# ST_Board.net
KiCad netlist of a schematic drawn in Altium Designer
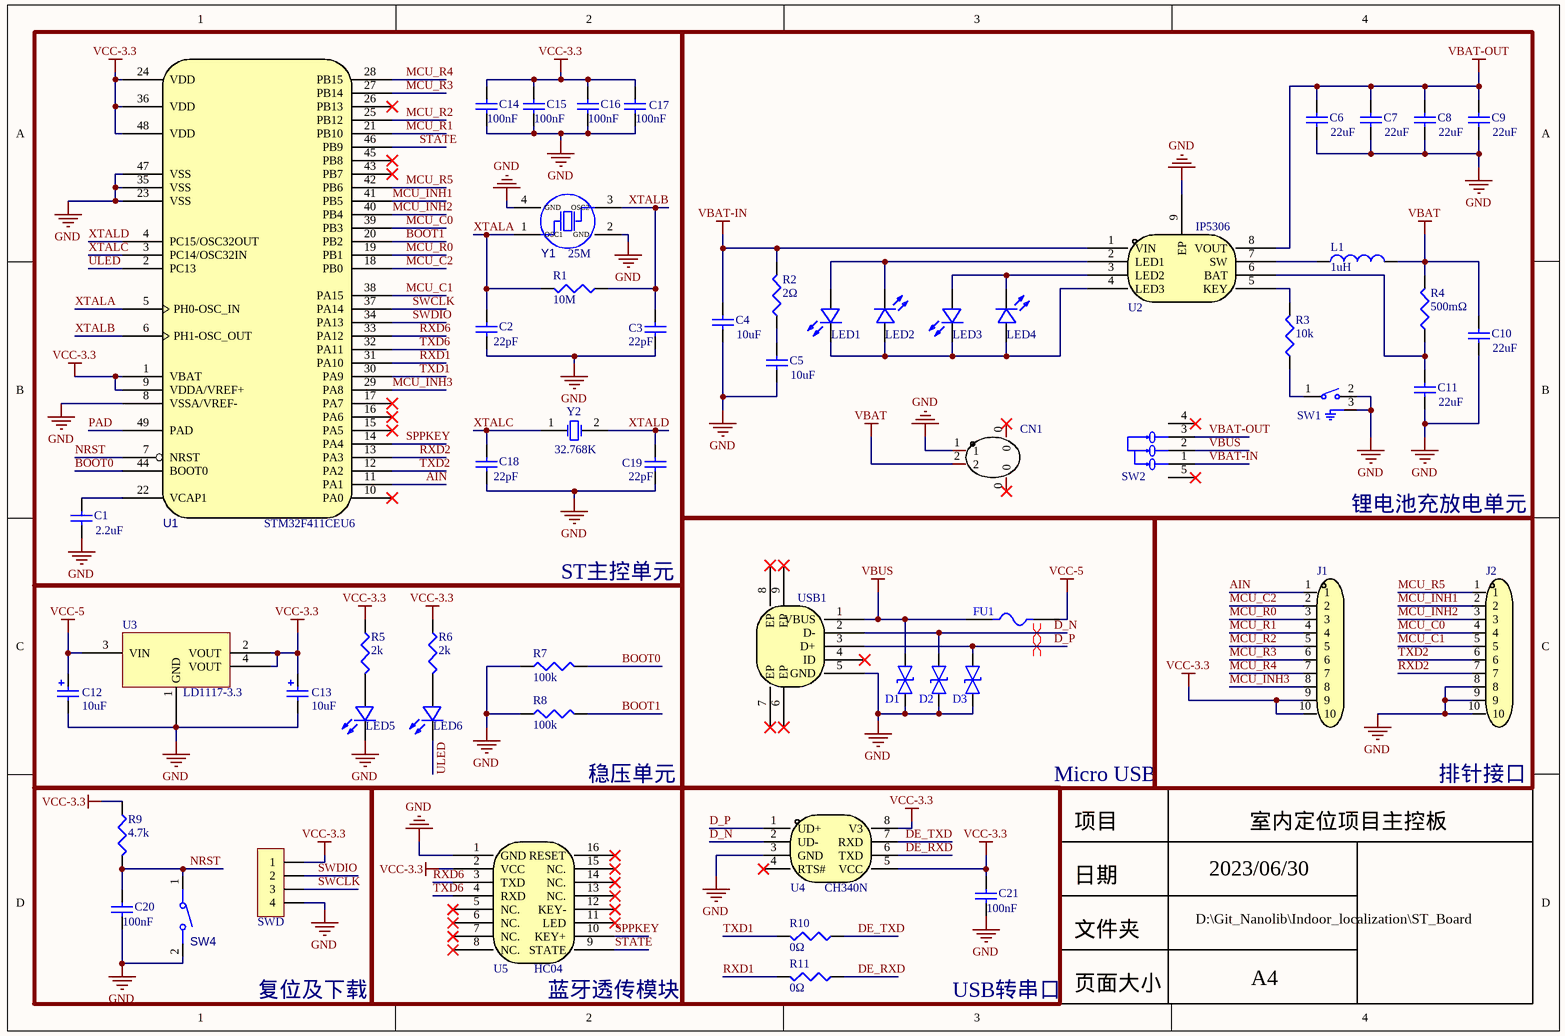
[diagram p0: ST_Board.SchDoc]

(export (version "E")
  (design (tool "Eeschema 10.0.6"))
  (components
    (comp (ref "C1")
      (value "2.2uF")
      (footprint "C0603")
      (description "Capacitor")
      (fields (field (name "Comment") "Cap") (field (name "PUBLISHER") "Altium Limited"))
      (libsource (lib "Miscellaneous Devices") (part "Cap"))
    )
    (comp (ref "C2")
      (value "22pF")
      (footprint "C0603")
      (description "Capacitor")
      (fields (field (name "Comment") "Cap") (field (name "PUBLISHER") "Altium Limited"))
      (libsource (lib "Miscellaneous Devices") (part "Cap"))
    )
    (comp (ref "C3")
      (value "22pF")
      (footprint "C0603")
      (description "Capacitor")
      (fields (field (name "Comment") "Cap") (field (name "PUBLISHER") "Altium Limited"))
      (libsource (lib "Miscellaneous Devices") (part "Cap"))
    )
    (comp (ref "C4")
      (value "10uF")
      (footprint "C0603")
      (description "Capacitor")
      (fields (field (name "Comment") "Cap") (field (name "PUBLISHER") "Altium Limited"))
      (libsource (lib "Miscellaneous Devices") (part "Cap"))
    )
    (comp (ref "C5")
      (value "10uF")
      (footprint "C0603")
      (description "Capacitor")
      (fields (field (name "Comment") "Cap") (field (name "PUBLISHER") "Altium Limited"))
      (libsource (lib "Miscellaneous Devices") (part "Cap"))
    )
    (comp (ref "C6")
      (value "22uF")
      (footprint "C1206")
      (description "Capacitor")
      (fields (field (name "Comment") "Cap") (field (name "PUBLISHER") "Altium Limited"))
      (libsource (lib "Miscellaneous Devices") (part "Cap"))
    )
    (comp (ref "C7")
      (value "22uF")
      (footprint "C1206")
      (description "Capacitor")
      (fields (field (name "Comment") "Cap") (field (name "PUBLISHER") "Altium Limited"))
      (libsource (lib "Miscellaneous Devices") (part "Cap"))
    )
    (comp (ref "C8")
      (value "22uF")
      (footprint "C1206")
      (description "Capacitor")
      (fields (field (name "Comment") "Cap") (field (name "PUBLISHER") "Altium Limited"))
      (libsource (lib "Miscellaneous Devices") (part "Cap"))
    )
    (comp (ref "C9")
      (value "22uF")
      (footprint "C1206")
      (description "Capacitor")
      (fields (field (name "Comment") "Cap") (field (name "PUBLISHER") "Altium Limited"))
      (libsource (lib "Miscellaneous Devices") (part "Cap"))
    )
    (comp (ref "C10")
      (value "22uF")
      (footprint "C1206")
      (description "Capacitor")
      (fields (field (name "Comment") "Cap") (field (name "PUBLISHER") "Altium Limited"))
      (libsource (lib "Miscellaneous Devices") (part "Cap"))
    )
    (comp (ref "C11")
      (value "22uF")
      (footprint "C1206")
      (description "Capacitor")
      (fields (field (name "Comment") "Cap") (field (name "PUBLISHER") "Altium Limited"))
      (libsource (lib "Miscellaneous Devices") (part "Cap"))
    )
    (comp (ref "C12")
      (value "10uF")
      (footprint "CAP-SMD_L3.2-W1.6-RD-C7171")
      (description "贴片钽电容")
      (fields (field (name "MANUFACTURER") "Kyocera AVX") (field (name "MANUFACTURER PART") "TAJA106K016RNJ"))
      (libsource (lib "Passive_Device") (part "Cap-TAJA"))
    )
    (comp (ref "C13")
      (value "10uF")
      (footprint "CAP-SMD_L3.2-W1.6-RD-C7171")
      (description "贴片钽电容")
      (fields (field (name "MANUFACTURER") "Kyocera AVX") (field (name "MANUFACTURER PART") "TAJA106K016RNJ"))
      (libsource (lib "Passive_Device") (part "Cap-TAJA"))
    )
    (comp (ref "C14")
      (value "100nF")
      (footprint "C0603")
      (description "Capacitor")
      (fields (field (name "Comment") "Cap") (field (name "PUBLISHER") "Altium Limited"))
      (libsource (lib "Miscellaneous Devices") (part "Cap"))
    )
    (comp (ref "C15")
      (value "100nF")
      (footprint "C0603")
      (description "Capacitor")
      (fields (field (name "Comment") "Cap") (field (name "PUBLISHER") "Altium Limited"))
      (libsource (lib "Miscellaneous Devices") (part "Cap"))
    )
    (comp (ref "C16")
      (value "100nF")
      (footprint "C0603")
      (description "Capacitor")
      (fields (field (name "Comment") "Cap") (field (name "PUBLISHER") "Altium Limited"))
      (libsource (lib "Miscellaneous Devices") (part "Cap"))
    )
    (comp (ref "C17")
      (value "100nF")
      (footprint "C0603")
      (description "Capacitor")
      (fields (field (name "Comment") "Cap") (field (name "PUBLISHER") "Altium Limited"))
      (libsource (lib "Miscellaneous Devices") (part "Cap"))
    )
    (comp (ref "C18")
      (value "22pF")
      (footprint "C0603")
      (description "Capacitor")
      (fields (field (name "Comment") "Cap") (field (name "PUBLISHER") "Altium Limited"))
      (libsource (lib "Miscellaneous Devices") (part "Cap"))
    )
    (comp (ref "C19")
      (value "22pF")
      (footprint "C0603")
      (description "Capacitor")
      (fields (field (name "Comment") "Cap") (field (name "PUBLISHER") "Altium Limited"))
      (libsource (lib "Miscellaneous Devices") (part "Cap"))
    )
    (comp (ref "C20")
      (value "100nF")
      (footprint "C0603")
      (description "Capacitor")
      (fields (field (name "Comment") "Cap") (field (name "PUBLISHER") "Altium Limited"))
      (libsource (lib "Miscellaneous Devices") (part "Cap"))
    )
    (comp (ref "C21")
      (value "100nF")
      (footprint "C0603")
      (description "Capacitor")
      (fields (field (name "Comment") "Cap") (field (name "PUBLISHER") "Altium Limited"))
      (libsource (lib "Miscellaneous Devices") (part "Cap"))
    )
    (comp (ref "CN1")
      (value "1.0T-2P卧贴")
      (footprint "CONN-SMD_1.0T-2P")
      (description "锂电池接口")
      (fields (field (name "MANUFACTURER") "BOOMELE(博穆精密)"))
      (libsource (lib "Component") (part "1.0T-2P卧贴"))
    )
    (comp (ref "D1")
      (value "LESD5D5.0CT1G")
      (footprint "SOD-523_L1.2-W0.8-LS1.6-BI")
      (description "静电放电(ESD)保护器件")
      (fields (field (name "DESIGNER") "U?"))
      (libsource (lib "Passive_Device") (part "LESD5D5.0CT1G"))
    )
    (comp (ref "D2")
      (value "LESD5D5.0CT1G")
      (footprint "SOD-523_L1.2-W0.8-LS1.6-BI")
      (description "静电放电(ESD)保护器件")
      (fields (field (name "DESIGNER") "U?"))
      (libsource (lib "Passive_Device") (part "LESD5D5.0CT1G"))
    )
    (comp (ref "D3")
      (value "LESD5D5.0CT1G")
      (footprint "SOD-523_L1.2-W0.8-LS1.6-BI")
      (description "静电放电(ESD)保护器件")
      (fields (field (name "DESIGNER") "U?"))
      (libsource (lib "Passive_Device") (part "LESD5D5.0CT1G"))
    )
    (comp (ref "FU1")
      (value "FUSE 1A")
      (footprint "F0805")
      (description "贴片保险丝")
      (fields (field (name "MANUFACTURER") "RUILON(瑞隆源)") (field (name "MANUFACTURER PART") "SMD0805P075TF"))
      (libsource (lib "Passive_Device") (part "FU"))
    )
    (comp (ref "J1")
      (value "Header 10X1")
      (footprint "HDR-TH_10P-P2.54-V-M")
      (description "10P*1接插件")
      (fields (field (name "DESIGNER") "U?"))
      (libsource (lib "Connector") (part "Header 10X1"))
    )
    (comp (ref "J2")
      (value "Header 10X1")
      (footprint "HDR-TH_10P-P2.54-V-M")
      (description "10P*1接插件")
      (fields (field (name "DESIGNER") "U?"))
      (libsource (lib "Connector") (part "Header 10X1"))
    )
    (comp (ref "L1")
      (value "1uH")
      (footprint "IND-SMD_L6.5-W6.5_IHLP-2525")
      (description "Inductor")
      (fields (field (name "PUBLISHER") "Altium Limited"))
      (libsource (lib "Miscellaneous Devices") (part "Inductor"))
    )
    (comp (ref "LED1")
      (value "NCD0603G2")
      (footprint "LED0603-RD")
      (fields (field (name "MANUFACTURER") "国星光电"))
      (libsource (lib "Component") (part "NCD0603G2"))
    )
    (comp (ref "LED2")
      (value "NCD0603G2")
      (footprint "LED0603-RD")
      (fields (field (name "MANUFACTURER") "国星光电"))
      (libsource (lib "Component") (part "NCD0603G2"))
    )
    (comp (ref "LED3")
      (value "NCD0603G2")
      (footprint "LED0603-RD")
      (fields (field (name "MANUFACTURER") "国星光电"))
      (libsource (lib "Component") (part "NCD0603G2"))
    )
    (comp (ref "LED4")
      (value "NCD0603G2")
      (footprint "LED0603-RD")
      (fields (field (name "MANUFACTURER") "国星光电"))
      (libsource (lib "Component") (part "NCD0603G2"))
    )
    (comp (ref "LED5")
      (value "NCD0603G2")
      (footprint "LED0603-RD")
      (description "LED")
      (fields (field (name "MANUFACTURER") "国星光电"))
      (libsource (lib "Component") (part "NCD0603G2"))
    )
    (comp (ref "LED6")
      (value "NCD0603G2")
      (footprint "LED0603-RD")
      (description "LED")
      (fields (field (name "MANUFACTURER") "国星光电"))
      (libsource (lib "Component") (part "NCD0603G2"))
    )
    (comp (ref "R1")
      (value "10M")
      (footprint "R0603")
      (description "Resistor")
      (fields (field (name "PUBLISHER") "Altium Limited"))
      (libsource (lib "Miscellaneous Devices") (part "Res3"))
    )
    (comp (ref "R2")
      (value "2Ω")
      (footprint "R0603")
      (description "Resistor")
      (fields (field (name "PUBLISHER") "Altium Limited"))
      (libsource (lib "Miscellaneous Devices") (part "Res3"))
    )
    (comp (ref "R3")
      (value "10k")
      (footprint "R0603")
      (description "Resistor")
      (fields (field (name "PUBLISHER") "Altium Limited"))
      (libsource (lib "Miscellaneous Devices") (part "Res3"))
    )
    (comp (ref "R4")
      (value "500mΩ")
      (footprint "R0603")
      (description "Resistor")
      (fields (field (name "PUBLISHER") "Altium Limited"))
      (libsource (lib "Miscellaneous Devices") (part "Res3"))
    )
    (comp (ref "R5")
      (value "2k")
      (footprint "R0603")
      (description "Resistor")
      (fields (field (name "PUBLISHER") "Altium Limited"))
      (libsource (lib "Miscellaneous Devices") (part "Res3"))
    )
    (comp (ref "R6")
      (value "2k")
      (footprint "R0603")
      (description "Resistor")
      (fields (field (name "PUBLISHER") "Altium Limited"))
      (libsource (lib "Miscellaneous Devices") (part "Res3"))
    )
    (comp (ref "R7")
      (value "100k")
      (footprint "R0603")
      (description "Resistor")
      (fields (field (name "PUBLISHER") "Altium Limited"))
      (libsource (lib "Miscellaneous Devices") (part "Res3"))
    )
    (comp (ref "R8")
      (value "100k")
      (footprint "R0603")
      (description "Resistor")
      (fields (field (name "PUBLISHER") "Altium Limited"))
      (libsource (lib "Miscellaneous Devices") (part "Res3"))
    )
    (comp (ref "R9")
      (value "4.7k")
      (footprint "R0603")
      (description "Resistor")
      (fields (field (name "PUBLISHER") "Altium Limited"))
      (libsource (lib "Miscellaneous Devices") (part "Res3"))
    )
    (comp (ref "R10")
      (value "0Ω")
      (footprint "R0603")
      (description "Resistor")
      (fields (field (name "PUBLISHER") "Altium Limited"))
      (libsource (lib "Miscellaneous Devices") (part "Res3"))
    )
    (comp (ref "R11")
      (value "0Ω")
      (footprint "R0603")
      (description "Resistor")
      (fields (field (name "PUBLISHER") "Altium Limited"))
      (libsource (lib "Miscellaneous Devices") (part "Res3"))
    )
    (comp (ref "SW1")
      (value "GT-TCB73B-H048-L1")
      (footprint "SW-TH_G-SWITCH_GT-TCB73B-H048-L1")
      (fields (field (name "MANUFACTURER") "G-Switch(品赞)"))
      (libsource (lib "Component") (part "GT-TCB73B-H048-L1"))
    )
    (comp (ref "SW2")
      (value "SK12D07VG3")
      (footprint "SW-TH_SK12D07VG3")
      (fields (field (name "MANUFACTURER") "SHOU HAN(首韩)"))
      (libsource (lib "Component") (part "SK12D07VG3"))
    )
    (comp (ref "SW4")
      (value "TS-1088-AR02016")
      (footprint "SW-SMD_L3.9-W3.0-P4.45")
      (fields (field (name "MANUFACTURER") "XUNPU(讯普)"))
      (libsource (lib "Switch") (part "TS-1088-AR02016"))
    )
    (comp (ref "SWD")
      (value "SWD")
      (footprint "HDR-TH_4P-P2.54-V-F")
      (description "4P接插件")
      (fields (field (name "版权归属") "源创客"))
      (libsource (lib "Connector") (part "Header 4"))
    )
    (comp (ref "U1")
      (value "STM32F411CEU6")
      (footprint "UFQFPN-48_L7.0-W7.0-P0.50-BL-EP")
      (fields (field (name "DESIGNER") "U?"))
      (libsource (lib "MCU") (part "STM32F411CEU6"))
    )
    (comp (ref "U2")
      (value "IP5306")
      (footprint "ESOP-8_L4.9-W3.9-P1.27-LS6.0-BL-EP")
      (fields (field (name "MANUFACTURER") "INJOINIC(英集芯)"))
      (libsource (lib "Component") (part "IP5306"))
    )
    (comp (ref "U3")
      (value "LD1117-3.3")
      (footprint "SOT-223-3_L6.5-W3.4-P2.30-LS7.0-BR")
      (description "低压差线性稳压器3.3V")
      (libsource (lib "Power") (part "LD1117-3.3"))
    )
    (comp (ref "U4")
      (value "CH340N")
      (footprint "SOP-8_L4.9-W3.9-P1.27-LS6.0-BL")
      (fields (field (name "DESIGNER") "U?"))
      (libsource (lib "IC_Device") (part "CH340N"))
    )
    (comp (ref "U5")
      (value "HC04")
      (footprint "HC-04")
      (description "SPP2.1+BLE5.0")
      (libsource (lib "IC_Device") (part "HC04"))
    )
    (comp (ref "USB1")
      (value "U-F-M5DD-W-2")
      (footprint "MICRO-USB-SMD_MICRO-USB-A17")
      (fields (field (name "MANUFACTURER") "韩国韩荣"))
      (libsource (lib "Component") (part "U-F-M5DD-W-2"))
    )
    (comp (ref "Y1")
      (value "25M")
      (footprint "OSC-SMD_4P-L3.2-W2.5-BL")
      (fields (field (name "MANUFACTURER") "TKD(泰晶)") (field (name "MANUFACTURER PART") "SX32Y025000BA1T"))
      (libsource (lib "Passive_Device") (part "XTAL 4pin"))
    )
    (comp (ref "Y2")
      (value "32.768K")
      (footprint "FC-135R_L3.2-W1.5")
      (description "晶振")
      (fields (field (name "PUBLISHER") "Altium Limited"))
      (libsource (lib "Passive_Device") (part "XTAL"))
    )
  )
  (nets
    (net (code "2") (name "/AIN") (class "Default")
      (node (ref "J1") (pin "1") (pinfunction "1_1") (pintype "passive"))
      (node (ref "U1") (pin "11") (pinfunction "PA1_11") (pintype "passive"))
    )
    (net (code "3") (name "/BOOT0") (class "Default")
      (node (ref "R7") (pin "2") (pinfunction "2_2") (pintype "passive"))
      (node (ref "U1") (pin "44") (pinfunction "BOOT0_44") (pintype "passive"))
    )
    (net (code "4") (name "/BOOT1") (class "Default")
      (node (ref "R8") (pin "2") (pinfunction "2_2") (pintype "passive"))
      (node (ref "U1") (pin "20") (pinfunction "PB2_20") (pintype "passive"))
    )
    (net (code "5") (name "/DE_RXD") (class "Default")
      (node (ref "R11") (pin "1") (pinfunction "1_1") (pintype "passive"))
      (node (ref "U4") (pin "6") (pinfunction "TXD_6") (pintype "passive"))
    )
    (net (code "6") (name "/DE_TXD") (class "Default")
      (node (ref "R10") (pin "1") (pinfunction "1_1") (pintype "passive"))
      (node (ref "U4") (pin "7") (pinfunction "RXD_7") (pintype "passive"))
    )
    (net (code "7") (name "/D_N") (class "Default")
      (node (ref "D2") (pin "2") (pinfunction "2_2") (pintype "passive"))
      (node (ref "U4") (pin "2") (pinfunction "UD-_2") (pintype "passive"))
      (node (ref "USB1") (pin "2") (pinfunction "D-_2") (pintype "passive"))
    )
    (net (code "8") (name "/D_P") (class "Default")
      (node (ref "D3") (pin "2") (pinfunction "2_2") (pintype "passive"))
      (node (ref "U4") (pin "1") (pinfunction "UD+_1") (pintype "passive"))
      (node (ref "USB1") (pin "3") (pinfunction "D+_3") (pintype "passive"))
    )
    (net (code "9") (name "/MCU_C0") (class "Default")
      (node (ref "J2") (pin "4") (pinfunction "4_4") (pintype "passive"))
      (node (ref "U1") (pin "39") (pinfunction "PB3_39") (pintype "passive"))
    )
    (net (code "10") (name "/MCU_C1") (class "Default")
      (node (ref "J2") (pin "5") (pinfunction "5_5") (pintype "passive"))
      (node (ref "U1") (pin "38") (pinfunction "PA15_38") (pintype "passive"))
    )
    (net (code "11") (name "/MCU_C2") (class "Default")
      (node (ref "J1") (pin "2") (pinfunction "2_2") (pintype "passive"))
      (node (ref "U1") (pin "18") (pinfunction "PB0_18") (pintype "passive"))
    )
    (net (code "12") (name "/MCU_INH1") (class "Default")
      (node (ref "J2") (pin "2") (pinfunction "2_2") (pintype "passive"))
      (node (ref "U1") (pin "41") (pinfunction "PB5_41") (pintype "passive"))
    )
    (net (code "13") (name "/MCU_INH2") (class "Default")
      (node (ref "J2") (pin "3") (pinfunction "3_3") (pintype "passive"))
      (node (ref "U1") (pin "40") (pinfunction "PB4_40") (pintype "passive"))
    )
    (net (code "14") (name "/MCU_INH3") (class "Default")
      (node (ref "J1") (pin "8") (pinfunction "8_8") (pintype "passive"))
      (node (ref "U1") (pin "29") (pinfunction "PA8_29") (pintype "passive"))
    )
    (net (code "15") (name "/MCU_R0") (class "Default")
      (node (ref "J1") (pin "3") (pinfunction "3_3") (pintype "passive"))
      (node (ref "U1") (pin "19") (pinfunction "PB1_19") (pintype "passive"))
    )
    (net (code "16") (name "/MCU_R1") (class "Default")
      (node (ref "J1") (pin "4") (pinfunction "4_4") (pintype "passive"))
      (node (ref "U1") (pin "21") (pinfunction "PB10_21") (pintype "passive"))
    )
    (net (code "17") (name "/MCU_R2") (class "Default")
      (node (ref "J1") (pin "5") (pinfunction "5_5") (pintype "passive"))
      (node (ref "U1") (pin "25") (pinfunction "PB12_25") (pintype "passive"))
    )
    (net (code "18") (name "/MCU_R3") (class "Default")
      (node (ref "J1") (pin "6") (pinfunction "6_6") (pintype "passive"))
      (node (ref "U1") (pin "27") (pinfunction "PB14_27") (pintype "passive"))
    )
    (net (code "19") (name "/MCU_R4") (class "Default")
      (node (ref "J1") (pin "7") (pinfunction "7_7") (pintype "passive"))
      (node (ref "U1") (pin "28") (pinfunction "PB15_28") (pintype "passive"))
    )
    (net (code "20") (name "/MCU_R5") (class "Default")
      (node (ref "J2") (pin "1") (pinfunction "1_1") (pintype "passive"))
      (node (ref "U1") (pin "42") (pinfunction "PB6_42") (pintype "passive"))
    )
    (net (code "21") (name "/NRST") (class "Default")
      (node (ref "C20") (pin "2") (pinfunction "2_2") (pintype "passive"))
      (node (ref "R9") (pin "2") (pinfunction "2_2") (pintype "passive"))
      (node (ref "SW4") (pin "1") (pinfunction "1_1") (pintype "passive"))
      (node (ref "U1") (pin "7") (pinfunction "NRST_7") (pintype "passive"))
    )
    (net (code "22") (name "/PAD") (class "Default")
      (node (ref "U1") (pin "49") (pinfunction "PAD_49") (pintype "passive"))
    )
    (net (code "23") (name "/RXD1") (class "Default")
      (node (ref "R11") (pin "2") (pinfunction "2_2") (pintype "passive"))
      (node (ref "U1") (pin "31") (pinfunction "PA10_31") (pintype "passive"))
    )
    (net (code "24") (name "/RXD2") (class "Default")
      (node (ref "J2") (pin "7") (pinfunction "7_7") (pintype "passive"))
      (node (ref "U1") (pin "13") (pinfunction "PA3_13") (pintype "passive"))
    )
    (net (code "25") (name "/RXD6") (class "Default")
      (node (ref "U1") (pin "33") (pinfunction "PA12_33") (pintype "passive"))
      (node (ref "U5") (pin "3") (pinfunction "TXD_3") (pintype "passive"))
    )
    (net (code "26") (name "/SPPKEY") (class "Default")
      (node (ref "U1") (pin "14") (pinfunction "PA4_14") (pintype "passive"))
      (node (ref "U5") (pin "10") (pinfunction "KEY+_10") (pintype "passive"))
    )
    (net (code "27") (name "/STATE") (class "Default")
      (node (ref "U1") (pin "46") (pinfunction "PB9_46") (pintype "passive"))
      (node (ref "U5") (pin "9") (pinfunction "STATE_9") (pintype "passive"))
    )
    (net (code "28") (name "/SWCLK") (class "Default")
      (node (ref "SWD") (pin "3") (pinfunction "3_3") (pintype "passive"))
      (node (ref "U1") (pin "37") (pinfunction "PA14_37") (pintype "passive"))
    )
    (net (code "29") (name "/SWDIO") (class "Default")
      (node (ref "SWD") (pin "2") (pinfunction "2_2") (pintype "passive"))
      (node (ref "U1") (pin "34") (pinfunction "PA13_34") (pintype "passive"))
    )
    (net (code "30") (name "/TXD1") (class "Default")
      (node (ref "R10") (pin "2") (pinfunction "2_2") (pintype "passive"))
      (node (ref "U1") (pin "30") (pinfunction "PA9_30") (pintype "passive"))
    )
    (net (code "31") (name "/TXD2") (class "Default")
      (node (ref "J2") (pin "6") (pinfunction "6_6") (pintype "passive"))
      (node (ref "U1") (pin "12") (pinfunction "PA2_12") (pintype "passive"))
    )
    (net (code "32") (name "/TXD6") (class "Default")
      (node (ref "U1") (pin "32") (pinfunction "PA11_32") (pintype "passive"))
      (node (ref "U5") (pin "4") (pinfunction "RXD_4") (pintype "passive"))
    )
    (net (code "33") (name "/ULED") (class "Default")
      (node (ref "LED6") (pin "1") (pinfunction "K_1") (pintype "passive"))
      (node (ref "U1") (pin "2") (pinfunction "PC13_2") (pintype "passive"))
    )
    (net (code "34") (name "/XTALA") (class "Default")
      (node (ref "C2") (pin "2") (pinfunction "2_2") (pintype "passive"))
      (node (ref "R1") (pin "2") (pinfunction "2_2") (pintype "passive"))
      (node (ref "U1") (pin "5") (pinfunction "PH0-OSC_IN_5") (pintype "passive"))
      (node (ref "Y1") (pin "1") (pinfunction "OSC1_1") (pintype "passive"))
    )
    (net (code "35") (name "/XTALB") (class "Default")
      (node (ref "C3") (pin "2") (pinfunction "2_2") (pintype "passive"))
      (node (ref "R1") (pin "1") (pinfunction "1_1") (pintype "passive"))
      (node (ref "U1") (pin "6") (pinfunction "PH1-OSC_OUT_6") (pintype "passive"))
      (node (ref "Y1") (pin "3") (pinfunction "OSC2_3") (pintype "passive"))
    )
    (net (code "36") (name "/XTALC") (class "Default")
      (node (ref "C18") (pin "2") (pinfunction "2_2") (pintype "passive"))
      (node (ref "U1") (pin "3") (pinfunction "PC14/OSC32IN_3") (pintype "passive"))
      (node (ref "Y2") (pin "1") (pinfunction "OSC1_1") (pintype "passive"))
    )
    (net (code "37") (name "/XTALD") (class "Default")
      (node (ref "C19") (pin "2") (pinfunction "2_2") (pintype "passive"))
      (node (ref "U1") (pin "4") (pinfunction "PC15/OSC32OUT_4") (pintype "passive"))
      (node (ref "Y2") (pin "2") (pinfunction "OSC2_2") (pintype "passive"))
    )
    (net (code "38") (name "GND") (class "Default")
      (node (ref "C1") (pin "1") (pinfunction "1_1") (pintype "passive"))
      (node (ref "C10") (pin "1") (pinfunction "1_1") (pintype "passive"))
      (node (ref "C11") (pin "1") (pinfunction "1_1") (pintype "passive"))
      (node (ref "C12") (pin "2") (pinfunction "2_2") (pintype "passive"))
      (node (ref "C13") (pin "2") (pinfunction "2_2") (pintype "passive"))
      (node (ref "C14") (pin "1") (pinfunction "1_1") (pintype "passive"))
      (node (ref "C15") (pin "1") (pinfunction "1_1") (pintype "passive"))
      (node (ref "C16") (pin "1") (pinfunction "1_1") (pintype "passive"))
      (node (ref "C17") (pin "1") (pinfunction "1_1") (pintype "passive"))
      (node (ref "C18") (pin "1") (pinfunction "1_1") (pintype "passive"))
      (node (ref "C19") (pin "1") (pinfunction "1_1") (pintype "passive"))
      (node (ref "C2") (pin "1") (pinfunction "1_1") (pintype "passive"))
      (node (ref "C20") (pin "1") (pinfunction "1_1") (pintype "passive"))
      (node (ref "C21") (pin "1") (pinfunction "1_1") (pintype "passive"))
      (node (ref "C3") (pin "1") (pinfunction "1_1") (pintype "passive"))
      (node (ref "C4") (pin "1") (pinfunction "1_1") (pintype "passive"))
      (node (ref "C5") (pin "1") (pinfunction "1_1") (pintype "passive"))
      (node (ref "C6") (pin "1") (pinfunction "1_1") (pintype "passive"))
      (node (ref "C7") (pin "1") (pinfunction "1_1") (pintype "passive"))
      (node (ref "C8") (pin "1") (pinfunction "1_1") (pintype "passive"))
      (node (ref "C9") (pin "1") (pinfunction "1_1") (pintype "passive"))
      (node (ref "CN1") (pin "1") (pinfunction "1_1") (pintype "passive"))
      (node (ref "D1") (pin "1") (pinfunction "1_1") (pintype "passive"))
      (node (ref "D2") (pin "1") (pinfunction "1_1") (pintype "passive"))
      (node (ref "D3") (pin "1") (pinfunction "1_1") (pintype "passive"))
      (node (ref "J2") (pin "10") (pinfunction "10_10") (pintype "passive"))
      (node (ref "J2") (pin "8") (pinfunction "8_8") (pintype "passive"))
      (node (ref "J2") (pin "9") (pinfunction "9_9") (pintype "passive"))
      (node (ref "LED5") (pin "1") (pinfunction "K_1") (pintype "passive"))
      (node (ref "R7") (pin "1") (pinfunction "1_1") (pintype "passive"))
      (node (ref "R8") (pin "1") (pinfunction "1_1") (pintype "passive"))
      (node (ref "SW1") (pin "2") (pinfunction "2_2") (pintype "passive"))
      (node (ref "SW1") (pin "3") (pinfunction "3_3") (pintype "passive"))
      (node (ref "SW4") (pin "2") (pinfunction "2_2") (pintype "passive"))
      (node (ref "SWD") (pin "4") (pinfunction "4_4") (pintype "passive"))
      (node (ref "U1") (pin "23") (pinfunction "VSS_23") (pintype "passive"))
      (node (ref "U1") (pin "35") (pinfunction "VSS_35") (pintype "passive"))
      (node (ref "U1") (pin "47") (pinfunction "VSS_47") (pintype "passive"))
      (node (ref "U1") (pin "8") (pinfunction "VSSA/VREF-_8") (pintype "passive"))
      (node (ref "U2") (pin "9") (pinfunction "EP_9") (pintype "passive"))
      (node (ref "U3") (pin "1") (pinfunction "GND_1") (pintype "passive"))
      (node (ref "U4") (pin "3") (pinfunction "GND_3") (pintype "passive"))
      (node (ref "U5") (pin "1") (pinfunction "GND_1") (pintype "passive"))
      (node (ref "USB1") (pin "5") (pinfunction "GND_5") (pintype "passive"))
      (node (ref "Y1") (pin "2") (pinfunction "GND_2") (pintype "passive"))
      (node (ref "Y1") (pin "4") (pinfunction "GND_4") (pintype "passive"))
    )
    (net (code "39") (name "Net-(C5-Pad2)") (class "Default")
      (node (ref "C5") (pin "2") (pinfunction "2_2") (pintype "passive"))
      (node (ref "R2") (pin "1") (pinfunction "1_1") (pintype "passive"))
    )
    (net (code "40") (name "Net-(LED1-A)") (class "Default")
      (node (ref "LED1") (pin "2") (pinfunction "A_2") (pintype "passive"))
      (node (ref "LED2") (pin "1") (pinfunction "K_1") (pintype "passive"))
      (node (ref "U2") (pin "2") (pinfunction "LED1_2") (pintype "passive"))
    )
    (net (code "41") (name "Net-(LED1-K)") (class "Default")
      (node (ref "LED1") (pin "1") (pinfunction "K_1") (pintype "passive"))
      (node (ref "LED2") (pin "2") (pinfunction "A_2") (pintype "passive"))
      (node (ref "LED3") (pin "1") (pinfunction "K_1") (pintype "passive"))
      (node (ref "LED4") (pin "2") (pinfunction "A_2") (pintype "passive"))
      (node (ref "U2") (pin "4") (pinfunction "LED3_4") (pintype "passive"))
    )
    (net (code "42") (name "Net-(LED3-A)") (class "Default")
      (node (ref "LED3") (pin "2") (pinfunction "A_2") (pintype "passive"))
      (node (ref "LED4") (pin "1") (pinfunction "K_1") (pintype "passive"))
      (node (ref "U2") (pin "3") (pinfunction "LED2_3") (pintype "passive"))
    )
    (net (code "43") (name "Net-(LED5-A)") (class "Default")
      (node (ref "LED5") (pin "2") (pinfunction "A_2") (pintype "passive"))
      (node (ref "R5") (pin "2") (pinfunction "2_2") (pintype "passive"))
    )
    (net (code "44") (name "Net-(LED6-A)") (class "Default")
      (node (ref "LED6") (pin "2") (pinfunction "A_2") (pintype "passive"))
      (node (ref "R6") (pin "2") (pinfunction "2_2") (pintype "passive"))
    )
    (net (code "45") (name "Net-(R3-Pad1)") (class "Default")
      (node (ref "R3") (pin "1") (pinfunction "1_1") (pintype "passive"))
      (node (ref "SW1") (pin "1") (pinfunction "1_1") (pintype "passive"))
    )
    (net (code "46") (name "Net-(U1-VCAP1)") (class "Default")
      (node (ref "C1") (pin "2") (pinfunction "2_2") (pintype "passive"))
      (node (ref "U1") (pin "22") (pinfunction "VCAP1_22") (pintype "passive"))
    )
    (net (code "47") (name "Net-(U2-BAT)") (class "Default")
      (node (ref "C11") (pin "2") (pinfunction "2_2") (pintype "passive"))
      (node (ref "R4") (pin "1") (pinfunction "1_1") (pintype "passive"))
      (node (ref "U2") (pin "6") (pinfunction "BAT_6") (pintype "passive"))
    )
    (net (code "48") (name "Net-(U2-KEY)") (class "Default")
      (node (ref "R3") (pin "2") (pinfunction "2_2") (pintype "passive"))
      (node (ref "U2") (pin "5") (pinfunction "KEY_5") (pintype "passive"))
    )
    (net (code "49") (name "Net-(U2-SW)") (class "Default")
      (node (ref "L1") (pin "1") (pinfunction "1_1") (pintype "passive"))
      (node (ref "U2") (pin "7") (pinfunction "SW_7") (pintype "passive"))
    )
    (net (code "50") (name "VBAT") (class "Default")
      (node (ref "C10") (pin "2") (pinfunction "2_2") (pintype "passive"))
      (node (ref "CN1") (pin "2") (pinfunction "2_2") (pintype "passive"))
      (node (ref "L1") (pin "2") (pinfunction "2_2") (pintype "passive"))
      (node (ref "R4") (pin "2") (pinfunction "2_2") (pintype "passive"))
    )
    (net (code "51") (name "VBAT-IN") (class "Default")
      (node (ref "C4") (pin "2") (pinfunction "2_2") (pintype "passive"))
      (node (ref "R2") (pin "2") (pinfunction "2_2") (pintype "passive"))
      (node (ref "SW2") (pin "1") (pinfunction "1_1") (pintype "passive"))
      (node (ref "U2") (pin "1") (pinfunction "VIN_1") (pintype "passive"))
    )
    (net (code "52") (name "VBAT-OUT") (class "Default")
      (node (ref "C6") (pin "2") (pinfunction "2_2") (pintype "passive"))
      (node (ref "C7") (pin "2") (pinfunction "2_2") (pintype "passive"))
      (node (ref "C8") (pin "2") (pinfunction "2_2") (pintype "passive"))
      (node (ref "C9") (pin "2") (pinfunction "2_2") (pintype "passive"))
      (node (ref "SW2") (pin "3") (pinfunction "3_3") (pintype "passive"))
      (node (ref "U2") (pin "8") (pinfunction "VOUT_8") (pintype "passive"))
    )
    (net (code "53") (name "VBUS") (class "Default")
      (node (ref "D1") (pin "2") (pinfunction "2_2") (pintype "passive"))
      (node (ref "FU1") (pin "1") (pinfunction "1_1") (pintype "passive"))
      (node (ref "SW2") (pin "2") (pinfunction "2_2") (pintype "passive"))
      (node (ref "USB1") (pin "1") (pinfunction "VBUS_1") (pintype "passive"))
    )
    (net (code "54") (name "VCC-3.3") (class "Default")
      (node (ref "C13") (pin "1") (pinfunction "1_1") (pintype "passive"))
      (node (ref "C14") (pin "2") (pinfunction "2_2") (pintype "passive"))
      (node (ref "C15") (pin "2") (pinfunction "2_2") (pintype "passive"))
      (node (ref "C16") (pin "2") (pinfunction "2_2") (pintype "passive"))
      (node (ref "C17") (pin "2") (pinfunction "2_2") (pintype "passive"))
      (node (ref "C21") (pin "2") (pinfunction "2_2") (pintype "passive"))
      (node (ref "J1") (pin "10") (pinfunction "10_10") (pintype "passive"))
      (node (ref "J1") (pin "9") (pinfunction "9_9") (pintype "passive"))
      (node (ref "R5") (pin "1") (pinfunction "1_1") (pintype "passive"))
      (node (ref "R6") (pin "1") (pinfunction "1_1") (pintype "passive"))
      (node (ref "R9") (pin "1") (pinfunction "1_1") (pintype "passive"))
      (node (ref "SWD") (pin "1") (pinfunction "1_1") (pintype "passive"))
      (node (ref "U1") (pin "1") (pinfunction "VBAT_1") (pintype "passive"))
      (node (ref "U1") (pin "24") (pinfunction "VDD_24") (pintype "passive"))
      (node (ref "U1") (pin "36") (pinfunction "VDD_36") (pintype "passive"))
      (node (ref "U1") (pin "48") (pinfunction "VDD_48") (pintype "passive"))
      (node (ref "U1") (pin "9") (pinfunction "VDDA/VREF+_9") (pintype "passive"))
      (node (ref "U3") (pin "2") (pinfunction "VOUT_2") (pintype "passive"))
      (node (ref "U3") (pin "4") (pinfunction "VOUT_4") (pintype "passive"))
      (node (ref "U4") (pin "5") (pinfunction "VCC_5") (pintype "passive"))
      (node (ref "U4") (pin "8") (pinfunction "V3_8") (pintype "passive"))
      (node (ref "U5") (pin "2") (pinfunction "VCC_2") (pintype "passive"))
    )
    (net (code "55") (name "VCC-5") (class "Default")
      (node (ref "C12") (pin "1") (pinfunction "1_1") (pintype "passive"))
      (node (ref "FU1") (pin "2") (pinfunction "2_2") (pintype "passive"))
      (node (ref "U3") (pin "3") (pinfunction "VIN_3") (pintype "passive"))
    )
    (net (code "56") (name "unconnected-(CN1-Pad0)") (class "Default")
      (node (ref "CN1") (pin "0") (pinfunction "0_0") (pintype "passive+no_connect"))
    )
    (net (code "57") (name "unconnected-(CN1-Pad0)_1") (class "Default")
      (node (ref "CN1") (pin "0") (pinfunction "0_0") (pintype "passive+no_connect"))
    )
    (net (code "58") (name "unconnected-(SW2-Pad4)") (class "Default")
      (node (ref "SW2") (pin "4") (pinfunction "4_4") (pintype "passive+no_connect"))
    )
    (net (code "59") (name "unconnected-(SW2-Pad5)") (class "Default")
      (node (ref "SW2") (pin "5") (pinfunction "5_5") (pintype "passive+no_connect"))
    )
    (net (code "60") (name "unconnected-(U1-PA0-Pad10)") (class "Default")
      (node (ref "U1") (pin "10") (pinfunction "PA0_10") (pintype "passive+no_connect"))
    )
    (net (code "61") (name "unconnected-(U1-PA5-Pad15)") (class "Default")
      (node (ref "U1") (pin "15") (pinfunction "PA5_15") (pintype "passive+no_connect"))
    )
    (net (code "62") (name "unconnected-(U1-PA6-Pad16)") (class "Default")
      (node (ref "U1") (pin "16") (pinfunction "PA6_16") (pintype "passive+no_connect"))
    )
    (net (code "63") (name "unconnected-(U1-PA7-Pad17)") (class "Default")
      (node (ref "U1") (pin "17") (pinfunction "PA7_17") (pintype "passive+no_connect"))
    )
    (net (code "64") (name "unconnected-(U1-PB7-Pad43)") (class "Default")
      (node (ref "U1") (pin "43") (pinfunction "PB7_43") (pintype "passive+no_connect"))
    )
    (net (code "65") (name "unconnected-(U1-PB8-Pad45)") (class "Default")
      (node (ref "U1") (pin "45") (pinfunction "PB8_45") (pintype "passive+no_connect"))
    )
    (net (code "66") (name "unconnected-(U1-PB13-Pad26)") (class "Default")
      (node (ref "U1") (pin "26") (pinfunction "PB13_26") (pintype "passive+no_connect"))
    )
    (net (code "67") (name "unconnected-(U4-RTS#-Pad4)") (class "Default")
      (node (ref "U4") (pin "4") (pinfunction "RTS#_4") (pintype "passive+no_connect"))
    )
    (net (code "68") (name "unconnected-(U5-KEY--Pad12)") (class "Default")
      (node (ref "U5") (pin "12") (pinfunction "KEY-_12") (pintype "passive+no_connect"))
    )
    (net (code "69") (name "unconnected-(U5-LED-Pad11)") (class "Default")
      (node (ref "U5") (pin "11") (pinfunction "LED_11") (pintype "passive+no_connect"))
    )
    (net (code "70") (name "unconnected-(U5-NC.-Pad5)") (class "Default")
      (node (ref "U5") (pin "5") (pinfunction "NC._5") (pintype "passive+no_connect"))
    )
    (net (code "71") (name "unconnected-(U5-NC.-Pad6)") (class "Default")
      (node (ref "U5") (pin "6") (pinfunction "NC._6") (pintype "passive+no_connect"))
    )
    (net (code "72") (name "unconnected-(U5-NC.-Pad7)") (class "Default")
      (node (ref "U5") (pin "7") (pinfunction "NC._7") (pintype "passive+no_connect"))
    )
    (net (code "73") (name "unconnected-(U5-NC.-Pad8)") (class "Default")
      (node (ref "U5") (pin "8") (pinfunction "NC._8") (pintype "passive+no_connect"))
    )
    (net (code "74") (name "unconnected-(U5-NC.-Pad13)") (class "Default")
      (node (ref "U5") (pin "13") (pinfunction "NC._13") (pintype "passive+no_connect"))
    )
    (net (code "75") (name "unconnected-(U5-NC.-Pad14)") (class "Default")
      (node (ref "U5") (pin "14") (pinfunction "NC._14") (pintype "passive+no_connect"))
    )
    (net (code "76") (name "unconnected-(U5-NC.-Pad15)") (class "Default")
      (node (ref "U5") (pin "15") (pinfunction "NC._15") (pintype "passive+no_connect"))
    )
    (net (code "77") (name "unconnected-(U5-RESET-Pad16)") (class "Default")
      (node (ref "U5") (pin "16") (pinfunction "RESET_16") (pintype "passive+no_connect"))
    )
    (net (code "78") (name "unconnected-(USB1-EP-Pad6)") (class "Default")
      (node (ref "USB1") (pin "6") (pinfunction "EP_6") (pintype "passive+no_connect"))
    )
    (net (code "79") (name "unconnected-(USB1-EP-Pad7)") (class "Default")
      (node (ref "USB1") (pin "7") (pinfunction "EP_7") (pintype "passive+no_connect"))
    )
    (net (code "80") (name "unconnected-(USB1-EP-Pad8)") (class "Default")
      (node (ref "USB1") (pin "8") (pinfunction "EP_8") (pintype "passive+no_connect"))
    )
    (net (code "81") (name "unconnected-(USB1-EP-Pad9)") (class "Default")
      (node (ref "USB1") (pin "9") (pinfunction "EP_9") (pintype "passive+no_connect"))
    )
    (net (code "82") (name "unconnected-(USB1-ID-Pad4)") (class "Default")
      (node (ref "USB1") (pin "4") (pinfunction "ID_4") (pintype "passive+no_connect"))
    )
  )
)
